# adc-rtc-shield.net
KiCad netlist of a schematic drawn in EAGLE
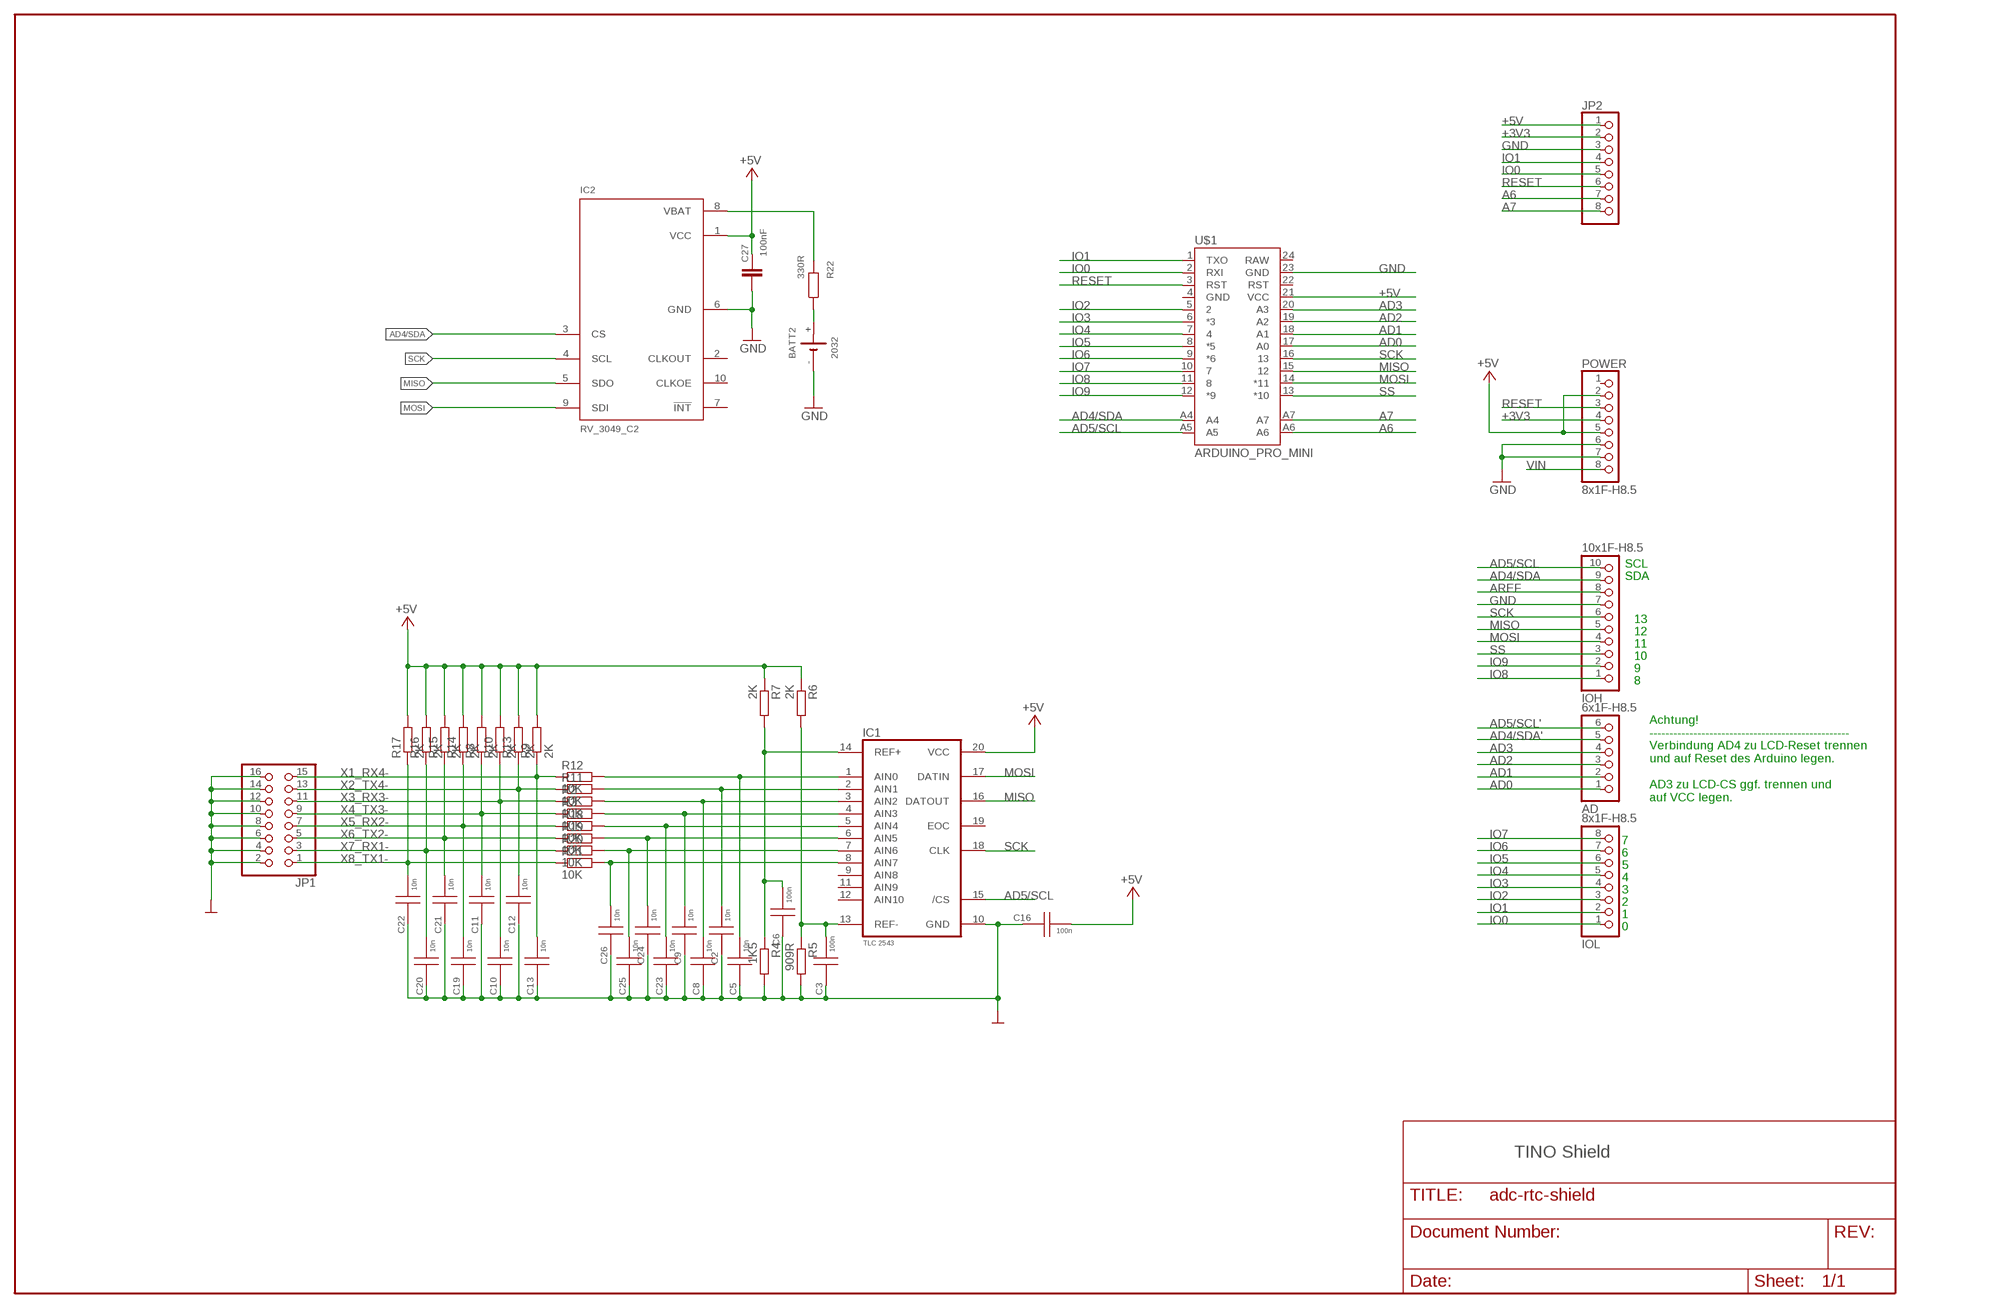
[diagram p0: schematic, sheet 1]

(export (version "E")
  (design (tool "Eeschema 10.0.6"))
  (components
    (comp (ref "AD")
      (value "6x1F-H8.5")
      (footprint "eagle-import:1X06")
      (libsource (lib "eagle-import") (part "PINHD-1X6"))
    )
    (comp (ref "BATT2")
      (value "2032")
      (footprint "eagle-import:2032_SMD")
      (libsource (lib "eagle-import") (part "CR2032_HOLDSMD"))
    )
    (comp (ref "C2")
      (value "10n")
      (footprint "eagle-import:0805-C")
      (libsource (lib "eagle-import") (part "C_KER"))
    )
    (comp (ref "C3")
      (value "100n")
      (footprint "eagle-import:0805-C")
      (libsource (lib "eagle-import") (part "C_KER"))
    )
    (comp (ref "C5")
      (value "10n")
      (footprint "eagle-import:0805-C")
      (libsource (lib "eagle-import") (part "C_KER"))
    )
    (comp (ref "C6")
      (value "100n")
      (footprint "eagle-import:0805-C")
      (libsource (lib "eagle-import") (part "C_KER"))
    )
    (comp (ref "C8")
      (value "10n")
      (footprint "eagle-import:0805-C")
      (libsource (lib "eagle-import") (part "C_KER"))
    )
    (comp (ref "C9")
      (value "10n")
      (footprint "eagle-import:0805-C")
      (libsource (lib "eagle-import") (part "C_KER"))
    )
    (comp (ref "C10")
      (value "10n")
      (footprint "eagle-import:0805-C")
      (libsource (lib "eagle-import") (part "C_KER"))
    )
    (comp (ref "C11")
      (value "10n")
      (footprint "eagle-import:0805-C")
      (libsource (lib "eagle-import") (part "C_KER"))
    )
    (comp (ref "C12")
      (value "10n")
      (footprint "eagle-import:0805-C")
      (libsource (lib "eagle-import") (part "C_KER"))
    )
    (comp (ref "C13")
      (value "10n")
      (footprint "eagle-import:0805-C")
      (libsource (lib "eagle-import") (part "C_KER"))
    )
    (comp (ref "C16")
      (value "100n")
      (footprint "eagle-import:0805-C")
      (libsource (lib "eagle-import") (part "C_KER"))
    )
    (comp (ref "C19")
      (value "10n")
      (footprint "eagle-import:0805-C")
      (libsource (lib "eagle-import") (part "C_KER"))
    )
    (comp (ref "C20")
      (value "10n")
      (footprint "eagle-import:0805-C")
      (libsource (lib "eagle-import") (part "C_KER"))
    )
    (comp (ref "C21")
      (value "10n")
      (footprint "eagle-import:0805-C")
      (libsource (lib "eagle-import") (part "C_KER"))
    )
    (comp (ref "C22")
      (value "10n")
      (footprint "eagle-import:0805-C")
      (libsource (lib "eagle-import") (part "C_KER"))
    )
    (comp (ref "C23")
      (value "10n")
      (footprint "eagle-import:0805-C")
      (libsource (lib "eagle-import") (part "C_KER"))
    )
    (comp (ref "C24")
      (value "10n")
      (footprint "eagle-import:0805-C")
      (libsource (lib "eagle-import") (part "C_KER"))
    )
    (comp (ref "C25")
      (value "10n")
      (footprint "eagle-import:0805-C")
      (libsource (lib "eagle-import") (part "C_KER"))
    )
    (comp (ref "C26")
      (value "10n")
      (footprint "eagle-import:0805-C")
      (libsource (lib "eagle-import") (part "C_KER"))
    )
    (comp (ref "C27")
      (value "100nF")
      (footprint "eagle-import:C0603")
      (libsource (lib "eagle-import") (part "C-EUC0603"))
    )
    (comp (ref "IC1")
      (value "TLC2543")
      (footprint "eagle-import:DIL_20")
      (libsource (lib "eagle-import") (part "TLC2543"))
    )
    (comp (ref "IC2")
      (value "RV_3049_C2")
      (footprint "eagle-import:5X3.2_10")
      (libsource (lib "eagle-import") (part "RV_3049_C2"))
    )
    (comp (ref "IOH")
      (value "10x1F-H8.5")
      (footprint "eagle-import:1X10")
      (libsource (lib "eagle-import") (part "PINHD-1X10_ARD"))
    )
    (comp (ref "IOL")
      (value "8x1F-H8.5")
      (footprint "eagle-import:1X08")
      (libsource (lib "eagle-import") (part "PINHD-1X8"))
    )
    (comp (ref "JP1")
      (value "PINHD-2X8/90")
      (footprint "eagle-import:2X08_90")
      (libsource (lib "eagle-import") (part "PINHD-2X8/90"))
    )
    (comp (ref "JP2")
      (value "PINHD-1X8/90")
      (footprint "eagle-import:1X08_90")
      (libsource (lib "eagle-import") (part "PINHD-1X8/90"))
    )
    (comp (ref "POWER")
      (value "8x1F-H8.5")
      (footprint "eagle-import:1X08")
      (libsource (lib "eagle-import") (part "PINHD-1X8"))
    )
    (comp (ref "R2")
      (value "10K")
      (footprint "eagle-import:R0603")
      (libsource (lib "eagle-import") (part "resistor_R-EU_R0603"))
    )
    (comp (ref "R3")
      (value "10K")
      (footprint "eagle-import:R0603")
      (libsource (lib "eagle-import") (part "resistor_R-EU_R0603"))
    )
    (comp (ref "R4")
      (value "1K5")
      (footprint "eagle-import:R0603")
      (libsource (lib "eagle-import") (part "resistor_R-EU_R0603"))
    )
    (comp (ref "R5")
      (value "909R")
      (footprint "eagle-import:R0603")
      (libsource (lib "eagle-import") (part "resistor_R-EU_R0603"))
    )
    (comp (ref "R6")
      (value "2K")
      (footprint "eagle-import:R0603")
      (libsource (lib "eagle-import") (part "resistor_R-EU_R0603"))
    )
    (comp (ref "R7")
      (value "2K")
      (footprint "eagle-import:R0603")
      (libsource (lib "eagle-import") (part "resistor_R-EU_R0603"))
    )
    (comp (ref "R8")
      (value "2K")
      (footprint "eagle-import:R0603")
      (libsource (lib "eagle-import") (part "resistor_R-EU_R0603"))
    )
    (comp (ref "R9")
      (value "2K")
      (footprint "eagle-import:R0603")
      (libsource (lib "eagle-import") (part "resistor_R-EU_R0603"))
    )
    (comp (ref "R10")
      (value "2K")
      (footprint "eagle-import:R0603")
      (libsource (lib "eagle-import") (part "resistor_R-EU_R0603"))
    )
    (comp (ref "R11")
      (value "10K")
      (footprint "eagle-import:R0603")
      (libsource (lib "eagle-import") (part "resistor_R-EU_R0603"))
    )
    (comp (ref "R12")
      (value "10K")
      (footprint "eagle-import:R0603")
      (libsource (lib "eagle-import") (part "resistor_R-EU_R0603"))
    )
    (comp (ref "R13")
      (value "2K")
      (footprint "eagle-import:R0603")
      (libsource (lib "eagle-import") (part "resistor_R-EU_R0603"))
    )
    (comp (ref "R14")
      (value "2K")
      (footprint "eagle-import:R0603")
      (libsource (lib "eagle-import") (part "resistor_R-EU_R0603"))
    )
    (comp (ref "R15")
      (value "2K")
      (footprint "eagle-import:R0603")
      (libsource (lib "eagle-import") (part "resistor_R-EU_R0603"))
    )
    (comp (ref "R16")
      (value "2K")
      (footprint "eagle-import:R0603")
      (libsource (lib "eagle-import") (part "resistor_R-EU_R0603"))
    )
    (comp (ref "R17")
      (value "2K")
      (footprint "eagle-import:R0603")
      (libsource (lib "eagle-import") (part "resistor_R-EU_R0603"))
    )
    (comp (ref "R18")
      (value "10K")
      (footprint "eagle-import:R0603")
      (libsource (lib "eagle-import") (part "resistor_R-EU_R0603"))
    )
    (comp (ref "R19")
      (value "10K")
      (footprint "eagle-import:R0603")
      (libsource (lib "eagle-import") (part "resistor_R-EU_R0603"))
    )
    (comp (ref "R20")
      (value "10K")
      (footprint "eagle-import:R0603")
      (libsource (lib "eagle-import") (part "resistor_R-EU_R0603"))
    )
    (comp (ref "R21")
      (value "10K")
      (footprint "eagle-import:R0603")
      (libsource (lib "eagle-import") (part "resistor_R-EU_R0603"))
    )
    (comp (ref "R22")
      (value "330R")
      (footprint "eagle-import:R0603")
      (libsource (lib "eagle-import") (part "R-EU_R0603"))
    )
    (comp (ref "U$1")
      (value "ARDUINO_PRO_MINI")
      (footprint "eagle-import:ARDUINO_PRO_MINI")
      (libsource (lib "eagle-import") (part "ARDUINO_PRO_MINI"))
    )
  )
  (nets
    (net (code "1") (name "+5V") (class "Default")
      (node (ref "C16") (pin "2") (pinfunction "2_2") (pintype "passive"))
      (node (ref "C27") (pin "1") (pinfunction "1_1") (pintype "passive"))
      (node (ref "IC1") (pin "20") (pinfunction "VCC_20") (pintype "power_in"))
      (node (ref "IC2") (pin "1") (pinfunction "VCC_1") (pintype "power_in"))
      (node (ref "JP2") (pin "1") (pinfunction "1_1") (pintype "passive"))
      (node (ref "POWER") (pin "2") (pinfunction "2_2") (pintype "passive"))
      (node (ref "POWER") (pin "5") (pinfunction "5_5") (pintype "passive"))
      (node (ref "R10") (pin "2") (pinfunction "2_2") (pintype "passive"))
      (node (ref "R13") (pin "2") (pinfunction "2_2") (pintype "passive"))
      (node (ref "R14") (pin "2") (pinfunction "2_2") (pintype "passive"))
      (node (ref "R15") (pin "2") (pinfunction "2_2") (pintype "passive"))
      (node (ref "R16") (pin "2") (pinfunction "2_2") (pintype "passive"))
      (node (ref "R17") (pin "2") (pinfunction "2_2") (pintype "passive"))
      (node (ref "R6") (pin "1") (pinfunction "1_1") (pintype "passive"))
      (node (ref "R7") (pin "1") (pinfunction "1_1") (pintype "passive"))
      (node (ref "R8") (pin "2") (pinfunction "2_2") (pintype "passive"))
      (node (ref "R9") (pin "2") (pinfunction "2_2") (pintype "passive"))
      (node (ref "U$1") (pin "21") (pinfunction "VCC_21") (pintype "bidirectional"))
    )
    (net (code "2") (name "/+3V3") (class "Default")
      (node (ref "JP2") (pin "2") (pinfunction "2_2") (pintype "passive"))
      (node (ref "POWER") (pin "4") (pinfunction "4_4") (pintype "passive"))
    )
    (net (code "3") (name "/A6") (class "Default")
      (node (ref "JP2") (pin "7") (pinfunction "7_7") (pintype "passive"))
      (node (ref "U$1") (pin "A6") (pinfunction "A6_A6") (pintype "bidirectional"))
    )
    (net (code "4") (name "/A7") (class "Default")
      (node (ref "JP2") (pin "8") (pinfunction "8_8") (pintype "passive"))
      (node (ref "U$1") (pin "A7") (pinfunction "A7_A7") (pintype "bidirectional"))
    )
    (net (code "5") (name "/AD0") (class "Default")
      (node (ref "AD") (pin "1") (pinfunction "1_1") (pintype "passive"))
      (node (ref "U$1") (pin "17") (pinfunction "A0_17") (pintype "bidirectional"))
    )
    (net (code "6") (name "/AD1") (class "Default")
      (node (ref "AD") (pin "2") (pinfunction "2_2") (pintype "passive"))
      (node (ref "U$1") (pin "18") (pinfunction "A1_18") (pintype "bidirectional"))
    )
    (net (code "7") (name "/AD2") (class "Default")
      (node (ref "AD") (pin "3") (pinfunction "3_3") (pintype "passive"))
      (node (ref "U$1") (pin "19") (pinfunction "A2_19") (pintype "bidirectional"))
    )
    (net (code "8") (name "/AD3") (class "Default")
      (node (ref "AD") (pin "4") (pinfunction "4_4") (pintype "passive"))
      (node (ref "U$1") (pin "20") (pinfunction "A3_20") (pintype "bidirectional"))
    )
    (net (code "9") (name "/AD4{slash}SDA'") (class "Default")
      (node (ref "AD") (pin "5") (pinfunction "5_5") (pintype "passive"))
    )
    (net (code "10") (name "/AD5{slash}SCL") (class "Default")
      (node (ref "IC1") (pin "15") (pinfunction "/CS_15") (pintype "input"))
      (node (ref "IOH") (pin "10") (pinfunction "10_10") (pintype "passive"))
      (node (ref "U$1") (pin "A5") (pinfunction "A5_A5") (pintype "bidirectional"))
    )
    (net (code "11") (name "/AD5{slash}SCL'") (class "Default")
      (node (ref "AD") (pin "6") (pinfunction "6_6") (pintype "passive"))
    )
    (net (code "12") (name "/AREF") (class "Default")
      (node (ref "IOH") (pin "8") (pinfunction "8_8") (pintype "passive"))
    )
    (net (code "13") (name "/IO0") (class "Default")
      (node (ref "IOL") (pin "1") (pinfunction "1_1") (pintype "passive"))
      (node (ref "JP2") (pin "5") (pinfunction "5_5") (pintype "passive"))
      (node (ref "U$1") (pin "2") (pinfunction "RXI_2") (pintype "bidirectional"))
    )
    (net (code "14") (name "/IO1") (class "Default")
      (node (ref "IOL") (pin "2") (pinfunction "2_2") (pintype "passive"))
      (node (ref "JP2") (pin "4") (pinfunction "4_4") (pintype "passive"))
      (node (ref "U$1") (pin "1") (pinfunction "TXO_1") (pintype "bidirectional"))
    )
    (net (code "15") (name "/IO2") (class "Default")
      (node (ref "IOL") (pin "3") (pinfunction "3_3") (pintype "passive"))
      (node (ref "U$1") (pin "5") (pinfunction "2_5") (pintype "bidirectional"))
    )
    (net (code "16") (name "/IO3") (class "Default")
      (node (ref "IOL") (pin "4") (pinfunction "4_4") (pintype "passive"))
      (node (ref "U$1") (pin "6") (pinfunction "*3_6") (pintype "bidirectional"))
    )
    (net (code "17") (name "/IO4") (class "Default")
      (node (ref "IOL") (pin "5") (pinfunction "5_5") (pintype "passive"))
      (node (ref "U$1") (pin "7") (pinfunction "4_7") (pintype "bidirectional"))
    )
    (net (code "18") (name "/IO5") (class "Default")
      (node (ref "IOL") (pin "6") (pinfunction "6_6") (pintype "passive"))
      (node (ref "U$1") (pin "8") (pinfunction "*5_8") (pintype "bidirectional"))
    )
    (net (code "19") (name "/IO6") (class "Default")
      (node (ref "IOL") (pin "7") (pinfunction "7_7") (pintype "passive"))
      (node (ref "U$1") (pin "9") (pinfunction "*6_9") (pintype "bidirectional"))
    )
    (net (code "20") (name "/IO7") (class "Default")
      (node (ref "IOL") (pin "8") (pinfunction "8_8") (pintype "passive"))
      (node (ref "U$1") (pin "10") (pinfunction "7_10") (pintype "bidirectional"))
    )
    (net (code "21") (name "/IO8") (class "Default")
      (node (ref "IOH") (pin "1") (pinfunction "1_1") (pintype "passive"))
      (node (ref "U$1") (pin "11") (pinfunction "8_11") (pintype "bidirectional"))
    )
    (net (code "22") (name "/IO9") (class "Default")
      (node (ref "IOH") (pin "2") (pinfunction "2_2") (pintype "passive"))
      (node (ref "U$1") (pin "12") (pinfunction "*9_12") (pintype "bidirectional"))
    )
    (net (code "23") (name "/RESET") (class "Default")
      (node (ref "JP2") (pin "6") (pinfunction "6_6") (pintype "passive"))
      (node (ref "POWER") (pin "3") (pinfunction "3_3") (pintype "passive"))
      (node (ref "U$1") (pin "3") (pinfunction "RST_3") (pintype "bidirectional"))
    )
    (net (code "24") (name "/SS") (class "Default")
      (node (ref "IOH") (pin "3") (pinfunction "3_3") (pintype "passive"))
      (node (ref "U$1") (pin "13") (pinfunction "*10_13") (pintype "bidirectional"))
    )
    (net (code "25") (name "/VIN") (class "Default")
      (node (ref "POWER") (pin "8") (pinfunction "8_8") (pintype "passive"))
    )
    (net (code "26") (name "/X1_RX4-") (class "Default")
      (node (ref "C13") (pin "2") (pinfunction "2_2") (pintype "passive"))
      (node (ref "JP1") (pin "15") (pinfunction "15_15") (pintype "passive"))
      (node (ref "R12") (pin "1") (pinfunction "1_1") (pintype "passive"))
      (node (ref "R9") (pin "1") (pinfunction "1_1") (pintype "passive"))
    )
    (net (code "27") (name "/X2_TX4-") (class "Default")
      (node (ref "C12") (pin "2") (pinfunction "2_2") (pintype "passive"))
      (node (ref "JP1") (pin "13") (pinfunction "13_13") (pintype "passive"))
      (node (ref "R11") (pin "1") (pinfunction "1_1") (pintype "passive"))
      (node (ref "R13") (pin "1") (pinfunction "1_1") (pintype "passive"))
    )
    (net (code "28") (name "/X3_RX3-") (class "Default")
      (node (ref "C10") (pin "2") (pinfunction "2_2") (pintype "passive"))
      (node (ref "JP1") (pin "11") (pinfunction "11_11") (pintype "passive"))
      (node (ref "R10") (pin "1") (pinfunction "1_1") (pintype "passive"))
      (node (ref "R2") (pin "1") (pinfunction "1_1") (pintype "passive"))
    )
    (net (code "29") (name "/X4_TX3-") (class "Default")
      (node (ref "C11") (pin "2") (pinfunction "2_2") (pintype "passive"))
      (node (ref "JP1") (pin "9") (pinfunction "9_9") (pintype "passive"))
      (node (ref "R3") (pin "1") (pinfunction "1_1") (pintype "passive"))
      (node (ref "R8") (pin "1") (pinfunction "1_1") (pintype "passive"))
    )
    (net (code "30") (name "/X5_RX2-") (class "Default")
      (node (ref "C19") (pin "2") (pinfunction "2_2") (pintype "passive"))
      (node (ref "JP1") (pin "7") (pinfunction "7_7") (pintype "passive"))
      (node (ref "R14") (pin "1") (pinfunction "1_1") (pintype "passive"))
      (node (ref "R18") (pin "1") (pinfunction "1_1") (pintype "passive"))
    )
    (net (code "31") (name "/X6_TX2-") (class "Default")
      (node (ref "C21") (pin "2") (pinfunction "2_2") (pintype "passive"))
      (node (ref "JP1") (pin "5") (pinfunction "5_5") (pintype "passive"))
      (node (ref "R15") (pin "1") (pinfunction "1_1") (pintype "passive"))
      (node (ref "R19") (pin "1") (pinfunction "1_1") (pintype "passive"))
    )
    (net (code "32") (name "/X7_RX1-") (class "Default")
      (node (ref "C20") (pin "2") (pinfunction "2_2") (pintype "passive"))
      (node (ref "JP1") (pin "3") (pinfunction "3_3") (pintype "passive"))
      (node (ref "R16") (pin "1") (pinfunction "1_1") (pintype "passive"))
      (node (ref "R20") (pin "1") (pinfunction "1_1") (pintype "passive"))
    )
    (net (code "33") (name "/X8_TX1-") (class "Default")
      (node (ref "C22") (pin "2") (pinfunction "2_2") (pintype "passive"))
      (node (ref "JP1") (pin "1") (pinfunction "1_1") (pintype "passive"))
      (node (ref "R17") (pin "1") (pinfunction "1_1") (pintype "passive"))
      (node (ref "R21") (pin "1") (pinfunction "1_1") (pintype "passive"))
    )
    (net (code "34") (name "AD4{slash}SDA") (class "Default")
      (node (ref "IC2") (pin "3") (pinfunction "CS_3") (pintype "input"))
      (node (ref "IOH") (pin "9") (pinfunction "9_9") (pintype "passive"))
      (node (ref "U$1") (pin "A4") (pinfunction "A4_A4") (pintype "bidirectional"))
    )
    (net (code "35") (name "GND") (class "Default")
      (node (ref "BATT2") (pin "-") (pinfunction "-_-") (pintype "passive"))
      (node (ref "C10") (pin "1") (pinfunction "1_1") (pintype "passive"))
      (node (ref "C11") (pin "1") (pinfunction "1_1") (pintype "passive"))
      (node (ref "C12") (pin "1") (pinfunction "1_1") (pintype "passive"))
      (node (ref "C13") (pin "1") (pinfunction "1_1") (pintype "passive"))
      (node (ref "C16") (pin "1") (pinfunction "1_1") (pintype "passive"))
      (node (ref "C19") (pin "1") (pinfunction "1_1") (pintype "passive"))
      (node (ref "C2") (pin "1") (pinfunction "1_1") (pintype "passive"))
      (node (ref "C20") (pin "1") (pinfunction "1_1") (pintype "passive"))
      (node (ref "C21") (pin "1") (pinfunction "1_1") (pintype "passive"))
      (node (ref "C22") (pin "1") (pinfunction "1_1") (pintype "passive"))
      (node (ref "C23") (pin "1") (pinfunction "1_1") (pintype "passive"))
      (node (ref "C24") (pin "1") (pinfunction "1_1") (pintype "passive"))
      (node (ref "C25") (pin "1") (pinfunction "1_1") (pintype "passive"))
      (node (ref "C26") (pin "1") (pinfunction "1_1") (pintype "passive"))
      (node (ref "C27") (pin "2") (pinfunction "2_2") (pintype "passive"))
      (node (ref "C3") (pin "1") (pinfunction "1_1") (pintype "passive"))
      (node (ref "C5") (pin "1") (pinfunction "1_1") (pintype "passive"))
      (node (ref "C6") (pin "1") (pinfunction "1_1") (pintype "passive"))
      (node (ref "C8") (pin "1") (pinfunction "1_1") (pintype "passive"))
      (node (ref "C9") (pin "1") (pinfunction "1_1") (pintype "passive"))
      (node (ref "IC1") (pin "10") (pinfunction "GND_10") (pintype "power_in"))
      (node (ref "IC2") (pin "6") (pinfunction "GND_6") (pintype "power_in"))
      (node (ref "IOH") (pin "7") (pinfunction "7_7") (pintype "passive"))
      (node (ref "JP1") (pin "10") (pinfunction "10_10") (pintype "passive"))
      (node (ref "JP1") (pin "12") (pinfunction "12_12") (pintype "passive"))
      (node (ref "JP1") (pin "14") (pinfunction "14_14") (pintype "passive"))
      (node (ref "JP1") (pin "16") (pinfunction "16_16") (pintype "passive"))
      (node (ref "JP1") (pin "2") (pinfunction "2_2") (pintype "passive"))
      (node (ref "JP1") (pin "4") (pinfunction "4_4") (pintype "passive"))
      (node (ref "JP1") (pin "6") (pinfunction "6_6") (pintype "passive"))
      (node (ref "JP1") (pin "8") (pinfunction "8_8") (pintype "passive"))
      (node (ref "JP2") (pin "3") (pinfunction "3_3") (pintype "passive"))
      (node (ref "POWER") (pin "6") (pinfunction "6_6") (pintype "passive"))
      (node (ref "POWER") (pin "7") (pinfunction "7_7") (pintype "passive"))
      (node (ref "R4") (pin "2") (pinfunction "2_2") (pintype "passive"))
      (node (ref "R5") (pin "2") (pinfunction "2_2") (pintype "passive"))
      (node (ref "U$1") (pin "23") (pinfunction "GND_23") (pintype "bidirectional"))
    )
    (net (code "36") (name "MISO") (class "Default")
      (node (ref "IC1") (pin "16") (pinfunction "DATOUT_16") (pintype "output"))
      (node (ref "IC2") (pin "5") (pinfunction "SDO_5") (pintype "output"))
      (node (ref "IOH") (pin "5") (pinfunction "5_5") (pintype "passive"))
      (node (ref "U$1") (pin "15") (pinfunction "12_15") (pintype "bidirectional"))
    )
    (net (code "37") (name "MOSI") (class "Default")
      (node (ref "IC1") (pin "17") (pinfunction "DATIN_17") (pintype "input"))
      (node (ref "IC2") (pin "9") (pinfunction "SDI_9") (pintype "input"))
      (node (ref "IOH") (pin "4") (pinfunction "4_4") (pintype "passive"))
      (node (ref "U$1") (pin "14") (pinfunction "*11_14") (pintype "bidirectional"))
    )
    (net (code "38") (name "Net-(BATT2-Pad+)") (class "Default")
      (node (ref "BATT2") (pin "+") (pinfunction "+_+") (pintype "passive"))
      (node (ref "R22") (pin "1") (pinfunction "1_1") (pintype "passive"))
    )
    (net (code "39") (name "Net-(IC1-AIN0)") (class "Default")
      (node (ref "C5") (pin "2") (pinfunction "2_2") (pintype "passive"))
      (node (ref "IC1") (pin "1") (pinfunction "AIN0_1") (pintype "input"))
      (node (ref "R12") (pin "2") (pinfunction "2_2") (pintype "passive"))
    )
    (net (code "40") (name "Net-(IC1-AIN1)") (class "Default")
      (node (ref "C2") (pin "2") (pinfunction "2_2") (pintype "passive"))
      (node (ref "IC1") (pin "2") (pinfunction "AIN1_2") (pintype "input"))
      (node (ref "R11") (pin "2") (pinfunction "2_2") (pintype "passive"))
    )
    (net (code "41") (name "Net-(IC1-AIN2)") (class "Default")
      (node (ref "C8") (pin "2") (pinfunction "2_2") (pintype "passive"))
      (node (ref "IC1") (pin "3") (pinfunction "AIN2_3") (pintype "input"))
      (node (ref "R2") (pin "2") (pinfunction "2_2") (pintype "passive"))
    )
    (net (code "42") (name "Net-(IC1-AIN3)") (class "Default")
      (node (ref "C9") (pin "2") (pinfunction "2_2") (pintype "passive"))
      (node (ref "IC1") (pin "4") (pinfunction "AIN3_4") (pintype "input"))
      (node (ref "R3") (pin "2") (pinfunction "2_2") (pintype "passive"))
    )
    (net (code "43") (name "Net-(IC1-AIN4)") (class "Default")
      (node (ref "C23") (pin "2") (pinfunction "2_2") (pintype "passive"))
      (node (ref "IC1") (pin "5") (pinfunction "AIN4_5") (pintype "input"))
      (node (ref "R18") (pin "2") (pinfunction "2_2") (pintype "passive"))
    )
    (net (code "44") (name "Net-(IC1-AIN5)") (class "Default")
      (node (ref "C24") (pin "2") (pinfunction "2_2") (pintype "passive"))
      (node (ref "IC1") (pin "6") (pinfunction "AIN5_6") (pintype "input"))
      (node (ref "R19") (pin "2") (pinfunction "2_2") (pintype "passive"))
    )
    (net (code "45") (name "Net-(IC1-AIN6)") (class "Default")
      (node (ref "C25") (pin "2") (pinfunction "2_2") (pintype "passive"))
      (node (ref "IC1") (pin "7") (pinfunction "AIN6_7") (pintype "input"))
      (node (ref "R20") (pin "2") (pinfunction "2_2") (pintype "passive"))
    )
    (net (code "46") (name "Net-(IC1-AIN7)") (class "Default")
      (node (ref "C26") (pin "2") (pinfunction "2_2") (pintype "passive"))
      (node (ref "IC1") (pin "8") (pinfunction "AIN7_8") (pintype "input"))
      (node (ref "R21") (pin "2") (pinfunction "2_2") (pintype "passive"))
    )
    (net (code "47") (name "Net-(IC1-REF+)") (class "Default")
      (node (ref "C6") (pin "2") (pinfunction "2_2") (pintype "passive"))
      (node (ref "IC1") (pin "14") (pinfunction "REF+_14") (pintype "input"))
      (node (ref "R4") (pin "1") (pinfunction "1_1") (pintype "passive"))
      (node (ref "R7") (pin "2") (pinfunction "2_2") (pintype "passive"))
    )
    (net (code "48") (name "Net-(IC1-REF-)") (class "Default")
      (node (ref "C3") (pin "2") (pinfunction "2_2") (pintype "passive"))
      (node (ref "IC1") (pin "13") (pinfunction "REF-_13") (pintype "input"))
      (node (ref "R5") (pin "1") (pinfunction "1_1") (pintype "passive"))
      (node (ref "R6") (pin "2") (pinfunction "2_2") (pintype "passive"))
    )
    (net (code "49") (name "Net-(IC2-VBAT)") (class "Default")
      (node (ref "IC2") (pin "8") (pinfunction "VBAT_8") (pintype "power_in"))
      (node (ref "R22") (pin "2") (pinfunction "2_2") (pintype "passive"))
    )
    (net (code "50") (name "SCK") (class "Default")
      (node (ref "IC1") (pin "18") (pinfunction "CLK_18") (pintype "input"))
      (node (ref "IC2") (pin "4") (pinfunction "SCL_4") (pintype "input"))
      (node (ref "IOH") (pin "6") (pinfunction "6_6") (pintype "passive"))
      (node (ref "U$1") (pin "16") (pinfunction "13_16") (pintype "bidirectional"))
    )
    (net (code "51") (name "unconnected-(IC1-AIN8-Pad9)") (class "Default")
      (node (ref "IC1") (pin "9") (pinfunction "AIN8_9") (pintype "input"))
    )
    (net (code "52") (name "unconnected-(IC1-AIN9-Pad11)") (class "Default")
      (node (ref "IC1") (pin "11") (pinfunction "AIN9_11") (pintype "input"))
    )
    (net (code "53") (name "unconnected-(IC1-AIN10-Pad12)") (class "Default")
      (node (ref "IC1") (pin "12") (pinfunction "AIN10_12") (pintype "input"))
    )
    (net (code "54") (name "unconnected-(IC1-EOC-Pad19)") (class "Default")
      (node (ref "IC1") (pin "19") (pinfunction "EOC_19") (pintype "output"))
    )
    (net (code "55") (name "unconnected-(IC2-CLKOE-Pad10)") (class "Default")
      (node (ref "IC2") (pin "10") (pinfunction "CLKOE_10") (pintype "input"))
    )
    (net (code "56") (name "unconnected-(IC2-CLKOUT-Pad2)") (class "Default")
      (node (ref "IC2") (pin "2") (pinfunction "CLKOUT_2") (pintype "output"))
    )
    (net (code "57") (name "unconnected-(IC2-~{INT}-Pad7)") (class "Default")
      (node (ref "IC2") (pin "7") (pinfunction "~{INT}_7") (pintype "open_collector"))
    )
    (net (code "58") (name "unconnected-(POWER-Pad1)") (class "Default")
      (node (ref "POWER") (pin "1") (pinfunction "1_1") (pintype "passive"))
    )
    (net (code "59") (name "unconnected-(U$1-GND-Pad4)") (class "Default")
      (node (ref "U$1") (pin "4") (pinfunction "GND_4") (pintype "bidirectional"))
    )
    (net (code "60") (name "unconnected-(U$1-RAW-Pad24)") (class "Default")
      (node (ref "U$1") (pin "24") (pinfunction "RAW_24") (pintype "bidirectional"))
    )
    (net (code "61") (name "unconnected-(U$1-RST-Pad22)") (class "Default")
      (node (ref "U$1") (pin "22") (pinfunction "RST_22") (pintype "bidirectional"))
    )
  )
)
